# anchor.net
KiCad netlist of a schematic drawn in EAGLE
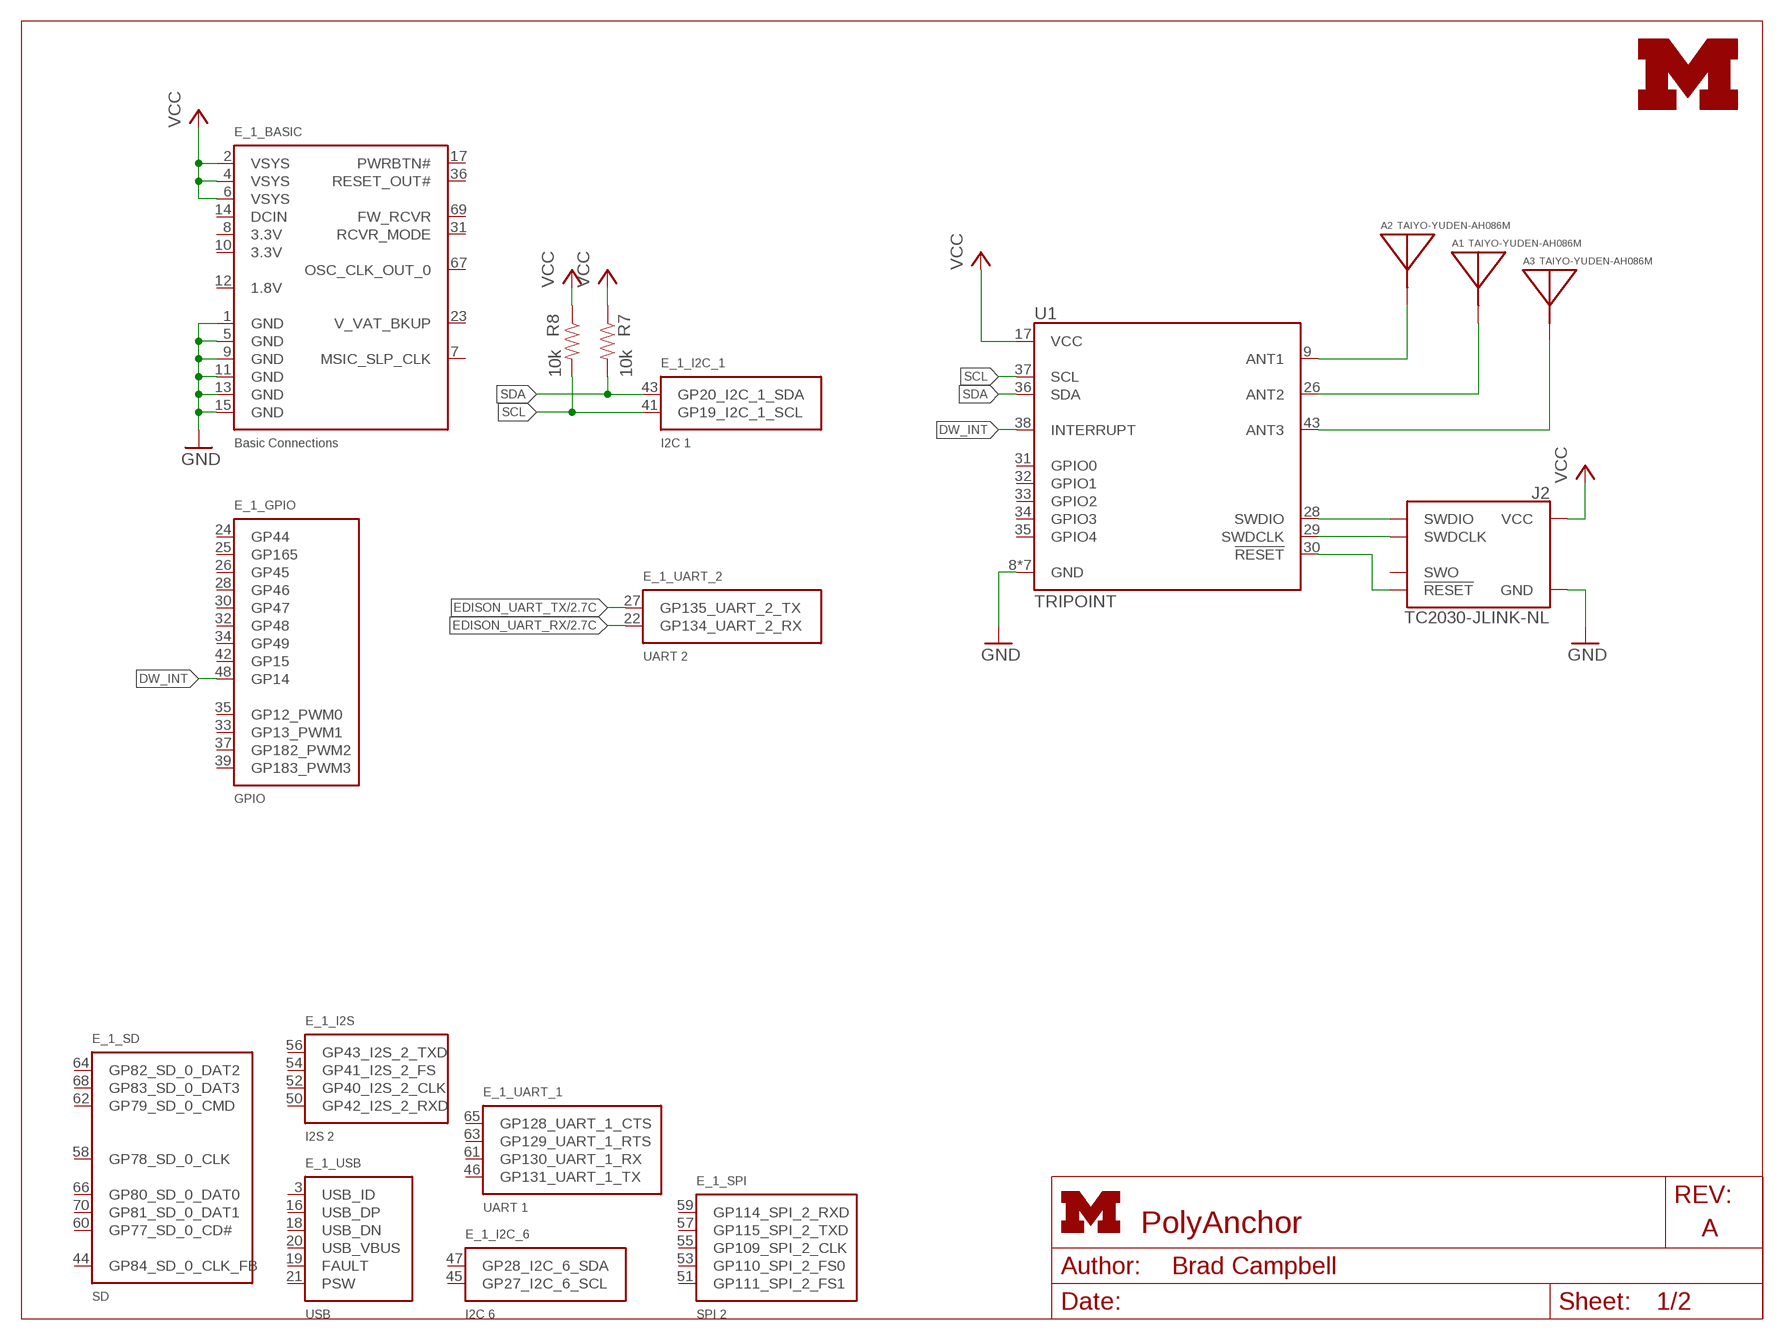
[diagram p0: schematic, sheet 1]
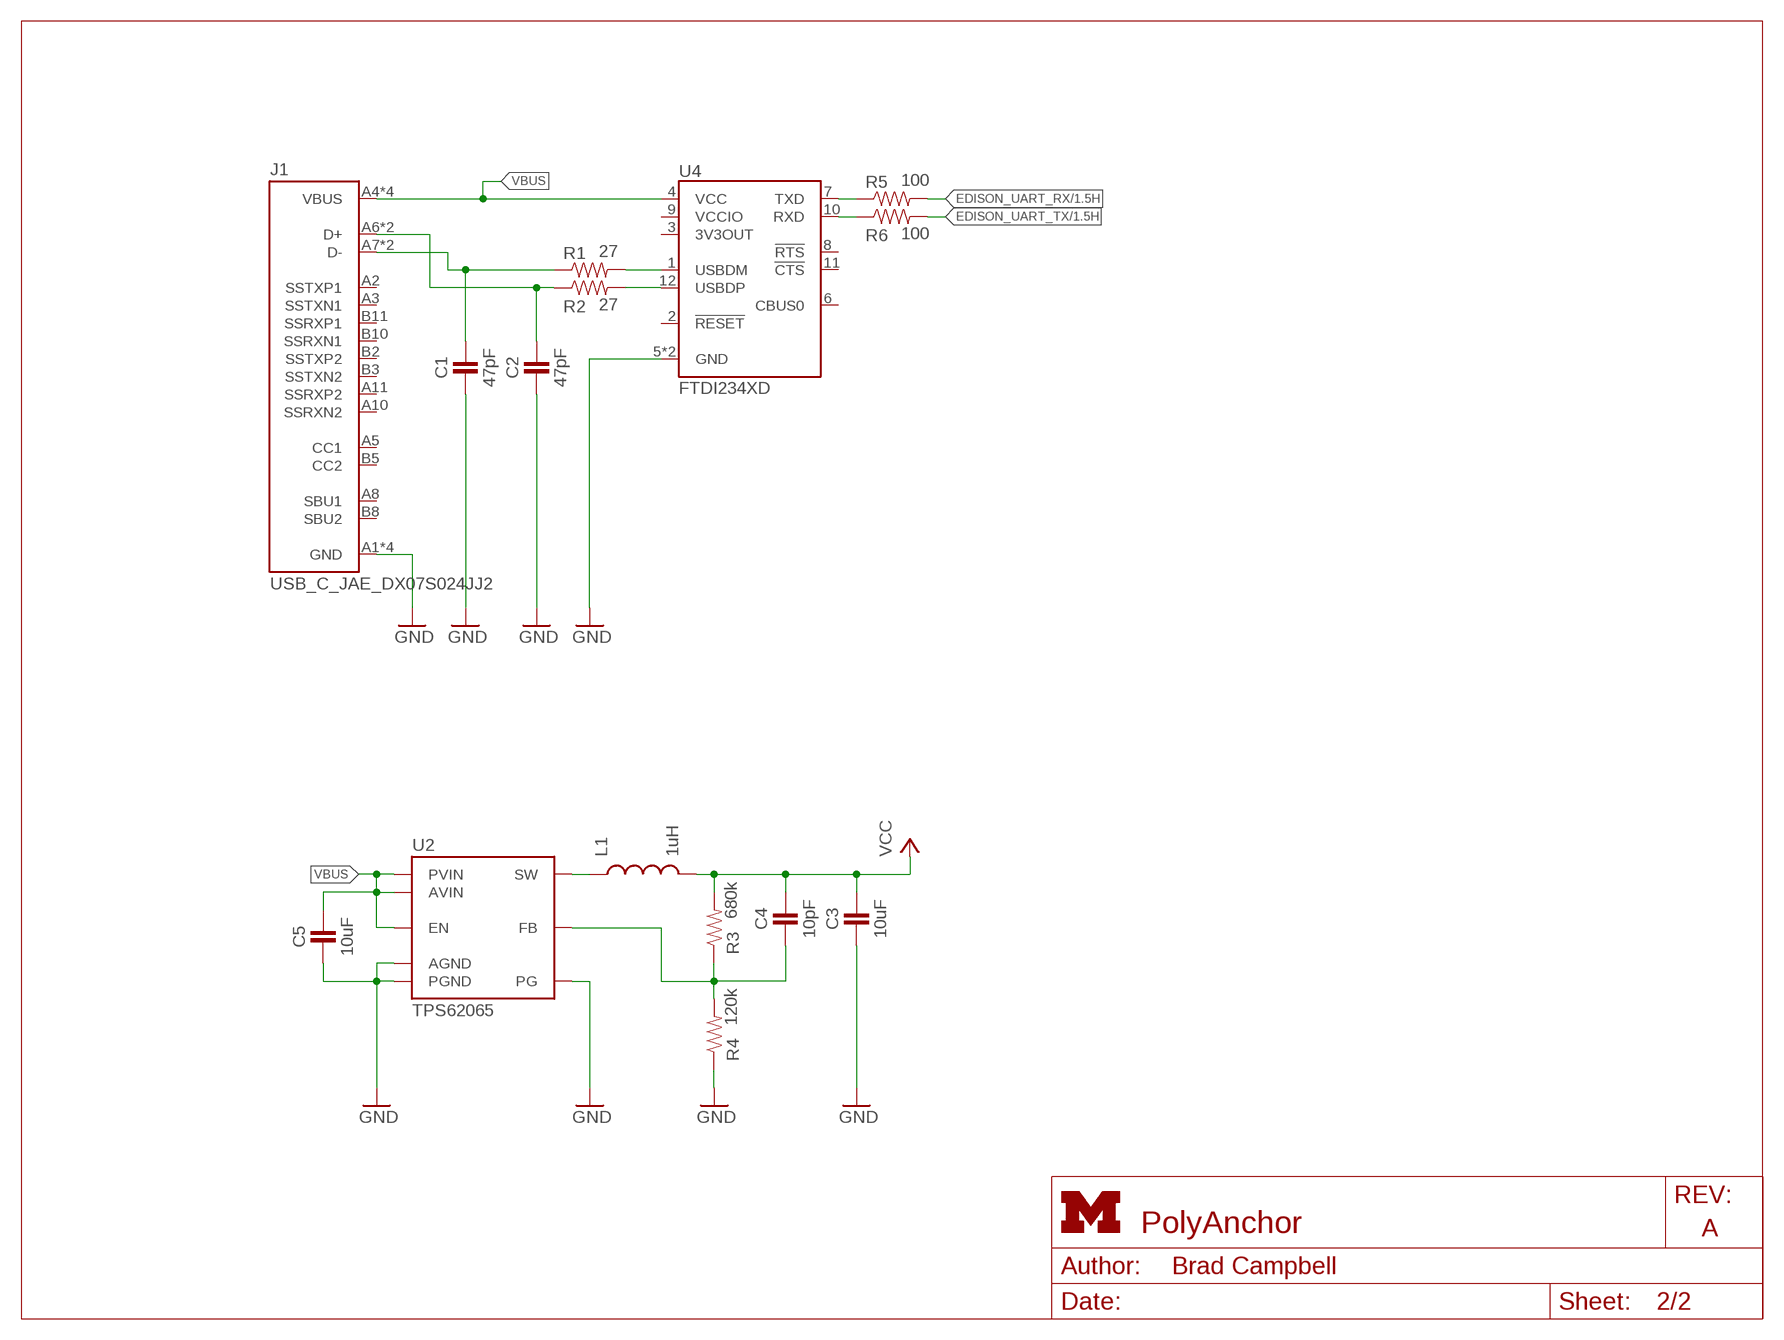
[diagram p1: schematic, sheet 2]

(export (version "E")
  (design (tool "Eeschema 10.0.6"))
  (components
    (comp (ref "C1")
      (value "47pF")
      (footprint "eagle-import:0402_CAP")
      (libsource (lib "eagle-import") (part "CAPACITOR"))
    )
    (comp (ref "C2")
      (value "47pF")
      (footprint "eagle-import:0402_CAP")
      (libsource (lib "eagle-import") (part "CAPACITOR"))
    )
    (comp (ref "C3")
      (value "10uF")
      (footprint "eagle-import:0603_CAP")
      (libsource (lib "eagle-import") (part "CAPACITOR0603_CAP"))
    )
    (comp (ref "C4")
      (value "10pF")
      (footprint "eagle-import:0402_CAP")
      (libsource (lib "eagle-import") (part "CAPACITOR"))
    )
    (comp (ref "C5")
      (value "10uF")
      (footprint "eagle-import:0603_CAP")
      (libsource (lib "eagle-import") (part "CAPACITOR0603_CAP"))
    )
    (comp (ref "J1")
      (value "USB_C_JAE_DX07S024JJ2")
      (footprint "eagle-import:DX07S024JJ2")
      (libsource (lib "eagle-import") (part "USB_C_JAE_DX07S024JJ2"))
    )
    (comp (ref "L1")
      (value "1uH")
      (footprint "eagle-import:1210")
      (libsource (lib "eagle-import") (part "INDUCTOR1210"))
    )
    (comp (ref "R1")
      (value "27")
      (footprint "eagle-import:0402_RES")
      (libsource (lib "eagle-import") (part "RESISTOR0402_RES"))
    )
    (comp (ref "R2")
      (value "27")
      (footprint "eagle-import:0402_RES")
      (libsource (lib "eagle-import") (part "RESISTOR0402_RES"))
    )
    (comp (ref "R3")
      (value "680k")
      (footprint "eagle-import:0402_RES")
      (libsource (lib "eagle-import") (part "RESISTOR0402_RES"))
    )
    (comp (ref "R4")
      (value "120k")
      (footprint "eagle-import:0402_RES")
      (libsource (lib "eagle-import") (part "RESISTOR0402_RES"))
    )
    (comp (ref "R5")
      (value "100")
      (footprint "eagle-import:0402_RES")
      (libsource (lib "eagle-import") (part "RESISTOR0402_RES"))
    )
    (comp (ref "R6")
      (value "100")
      (footprint "eagle-import:0402_RES")
      (libsource (lib "eagle-import") (part "RESISTOR0402_RES"))
    )
    (comp (ref "U2")
      (value "TPS62065")
      (footprint "eagle-import:S-PWSON-N8")
      (libsource (lib "eagle-import") (part "TPS62065"))
    )
    (comp (ref "U4")
      (value "FTDI234XD")
      (footprint "eagle-import:DFN-12_3MM")
      (libsource (lib "eagle-import") (part "FTDI234XD"))
    )
    (comp (ref "A1")
      (value "TAIYO-YUDEN-AH086M")
      (footprint "eagle-import:TAIYO-YUDEN-AH086M")
      (libsource (lib "eagle-import") (part "TAIYO-YUDEN-AH086M"))
    )
    (comp (ref "A2")
      (value "TAIYO-YUDEN-AH086M")
      (footprint "eagle-import:TAIYO-YUDEN-AH086M")
      (libsource (lib "eagle-import") (part "TAIYO-YUDEN-AH086M"))
    )
    (comp (ref "A3")
      (value "TAIYO-YUDEN-AH086M")
      (footprint "eagle-import:TAIYO-YUDEN-AH086M")
      (libsource (lib "eagle-import") (part "TAIYO-YUDEN-AH086M"))
    )
    (comp (ref "E_1")
      (value "EDISON_CONNECTOR_SEGMENTED")
      (footprint "eagle-import:EDISON_DAUGHTER")
      (libsource (lib "eagle-import") (part "EDISON_CONNECTOR_SEGMENTED"))
    )
    (comp (ref "J2")
      (value "TC2030-JLINK-NL")
      (footprint "eagle-import:TC2030-IDC-NL")
      (libsource (lib "eagle-import") (part "TC2030-JLINK-NL"))
    )
    (comp (ref "LOGO1")
      (value "UMICH_SOLID_MEDIUM")
      (footprint "eagle-import:UMICH_SOLID_200MIL")
      (libsource (lib "eagle-import") (part "UMICH_SOLID_MEDIUM"))
    )
    (comp (ref "R7")
      (value "10k")
      (footprint "eagle-import:0402_RES")
      (libsource (lib "eagle-import") (part "RESISTOR0402_RES"))
    )
    (comp (ref "R8")
      (value "10k")
      (footprint "eagle-import:0402_RES")
      (libsource (lib "eagle-import") (part "RESISTOR0402_RES"))
    )
    (comp (ref "U1")
      (value "TRIPOINT")
      (footprint "eagle-import:TRIPOINT")
      (libsource (lib "eagle-import") (part "TRIPOINT"))
    )
  )
  (nets
    (net (code "1") (name "DW_INT") (class "Default")
      (node (ref "E_1") (pin "48") (pinfunction "GP14_48") (pintype "bidirectional"))
      (node (ref "U1") (pin "38") (pinfunction "INTERRUPT_38") (pintype "bidirectional"))
    )
    (net (code "2") (name "EDISON_UART_RX") (class "Default")
      (node (ref "E_1") (pin "22") (pinfunction "GP134_UART_2_RX_22") (pintype "bidirectional"))
      (node (ref "R5") (pin "2") (pinfunction "2_2") (pintype "passive"))
    )
    (net (code "3") (name "EDISON_UART_TX") (class "Default")
      (node (ref "E_1") (pin "27") (pinfunction "GP135_UART_2_TX_27") (pintype "bidirectional"))
      (node (ref "R6") (pin "2") (pinfunction "2_2") (pintype "passive"))
    )
    (net (code "4") (name "GND") (class "Default")
      (node (ref "C1") (pin "2") (pinfunction "2_2") (pintype "bidirectional"))
      (node (ref "C2") (pin "2") (pinfunction "2_2") (pintype "bidirectional"))
      (node (ref "C3") (pin "2") (pinfunction "2_2") (pintype "bidirectional"))
      (node (ref "C5") (pin "2") (pinfunction "2_2") (pintype "bidirectional"))
      (node (ref "E_1") (pin "1") (pinfunction "GND_1") (pintype "bidirectional"))
      (node (ref "E_1") (pin "11") (pinfunction "GND_11") (pintype "bidirectional"))
      (node (ref "E_1") (pin "13") (pinfunction "GND_13") (pintype "bidirectional"))
      (node (ref "E_1") (pin "15") (pinfunction "GND_15") (pintype "bidirectional"))
      (node (ref "E_1") (pin "5") (pinfunction "GND_5") (pintype "bidirectional"))
      (node (ref "E_1") (pin "9") (pinfunction "GND_9") (pintype "bidirectional"))
      (node (ref "J1") (pin "A1") (pinfunction "GND_A1") (pintype "bidirectional"))
      (node (ref "J1") (pin "A12") (pinfunction "GND_A12") (pintype "bidirectional"))
      (node (ref "J1") (pin "B1") (pinfunction "GND_B1") (pintype "bidirectional"))
      (node (ref "J1") (pin "B12") (pinfunction "GND_B12") (pintype "bidirectional"))
      (node (ref "J2") (pin "5") (pinfunction "GND_5") (pintype "bidirectional"))
      (node (ref "R4") (pin "1") (pinfunction "1_1") (pintype "passive"))
      (node (ref "U1") (pin "10") (pinfunction "GND_10") (pintype "bidirectional"))
      (node (ref "U1") (pin "18") (pinfunction "GND_18") (pintype "bidirectional"))
      (node (ref "U1") (pin "25") (pinfunction "GND_25") (pintype "bidirectional"))
      (node (ref "U1") (pin "27") (pinfunction "GND_27") (pintype "bidirectional"))
      (node (ref "U1") (pin "42") (pinfunction "GND_42") (pintype "bidirectional"))
      (node (ref "U1") (pin "44") (pinfunction "GND_44") (pintype "bidirectional"))
      (node (ref "U1") (pin "8") (pinfunction "GND_8") (pintype "bidirectional"))
      (node (ref "U2") (pin "1") (pinfunction "PGND_1") (pintype "bidirectional"))
      (node (ref "U2") (pin "3") (pinfunction "AGND_3") (pintype "bidirectional"))
      (node (ref "U2") (pin "6") (pinfunction "PG_6") (pintype "bidirectional"))
      (node (ref "U2") (pin "P$1") (pinfunction "PGND_P$1") (pintype "bidirectional"))
      (node (ref "U4") (pin "13") (pinfunction "GND_13") (pintype "bidirectional"))
      (node (ref "U4") (pin "5") (pinfunction "GND_5") (pintype "bidirectional"))
    )
    (net (code "5") (name "Net-(A1-ANTENNA)") (class "Default")
      (node (ref "A1") (pin "A") (pinfunction "ANTENNA_A") (pintype "bidirectional"))
      (node (ref "U1") (pin "26") (pinfunction "ANT2_26") (pintype "bidirectional"))
    )
    (net (code "6") (name "Net-(A2-ANTENNA)") (class "Default")
      (node (ref "A2") (pin "A") (pinfunction "ANTENNA_A") (pintype "bidirectional"))
      (node (ref "U1") (pin "9") (pinfunction "ANT1_9") (pintype "bidirectional"))
    )
    (net (code "7") (name "Net-(A3-ANTENNA)") (class "Default")
      (node (ref "A3") (pin "A") (pinfunction "ANTENNA_A") (pintype "bidirectional"))
      (node (ref "U1") (pin "43") (pinfunction "ANT3_43") (pintype "bidirectional"))
    )
    (net (code "8") (name "Net-(C1-Pad1)") (class "Default")
      (node (ref "C1") (pin "1") (pinfunction "1_1") (pintype "bidirectional"))
      (node (ref "J1") (pin "A7") (pinfunction "D-_A7") (pintype "bidirectional"))
      (node (ref "J1") (pin "B7") (pinfunction "D-_B7") (pintype "bidirectional"))
      (node (ref "R1") (pin "1") (pinfunction "1_1") (pintype "passive"))
    )
    (net (code "9") (name "Net-(C2-Pad1)") (class "Default")
      (node (ref "C2") (pin "1") (pinfunction "1_1") (pintype "bidirectional"))
      (node (ref "J1") (pin "A6") (pinfunction "D+_A6") (pintype "bidirectional"))
      (node (ref "J1") (pin "B6") (pinfunction "D+_B6") (pintype "bidirectional"))
      (node (ref "R2") (pin "1") (pinfunction "1_1") (pintype "passive"))
    )
    (net (code "10") (name "Net-(J2-SWDCLK)") (class "Default")
      (node (ref "J2") (pin "4") (pinfunction "SWDCLK_4") (pintype "bidirectional"))
      (node (ref "U1") (pin "29") (pinfunction "SWDCLK_29") (pintype "bidirectional"))
    )
    (net (code "11") (name "Net-(J2-SWDIO)") (class "Default")
      (node (ref "J2") (pin "2") (pinfunction "SWDIO_2") (pintype "bidirectional"))
      (node (ref "U1") (pin "28") (pinfunction "SWDIO_28") (pintype "bidirectional"))
    )
    (net (code "12") (name "Net-(J2-~{RESET})") (class "Default")
      (node (ref "J2") (pin "3") (pinfunction "~{RESET}_3") (pintype "bidirectional"))
      (node (ref "U1") (pin "30") (pinfunction "~{RESET}_30") (pintype "bidirectional"))
    )
    (net (code "13") (name "Net-(U2-FB)") (class "Default")
      (node (ref "C4") (pin "2") (pinfunction "2_2") (pintype "bidirectional"))
      (node (ref "R3") (pin "1") (pinfunction "1_1") (pintype "passive"))
      (node (ref "R4") (pin "2") (pinfunction "2_2") (pintype "passive"))
      (node (ref "U2") (pin "4") (pinfunction "FB_4") (pintype "bidirectional"))
    )
    (net (code "14") (name "Net-(U2-SW)") (class "Default")
      (node (ref "L1") (pin "1") (pinfunction "1_1") (pintype "passive"))
      (node (ref "U2") (pin "2") (pinfunction "SW_2") (pintype "bidirectional"))
    )
    (net (code "15") (name "Net-(U4-RXD)") (class "Default")
      (node (ref "R6") (pin "1") (pinfunction "1_1") (pintype "passive"))
      (node (ref "U4") (pin "10") (pinfunction "RXD_10") (pintype "bidirectional"))
    )
    (net (code "16") (name "Net-(U4-TXD)") (class "Default")
      (node (ref "R5") (pin "1") (pinfunction "1_1") (pintype "passive"))
      (node (ref "U4") (pin "7") (pinfunction "TXD_7") (pintype "bidirectional"))
    )
    (net (code "17") (name "Net-(U4-USBDM)") (class "Default")
      (node (ref "R1") (pin "2") (pinfunction "2_2") (pintype "passive"))
      (node (ref "U4") (pin "1") (pinfunction "USBDM_1") (pintype "bidirectional"))
    )
    (net (code "18") (name "Net-(U4-USBDP)") (class "Default")
      (node (ref "R2") (pin "2") (pinfunction "2_2") (pintype "passive"))
      (node (ref "U4") (pin "12") (pinfunction "USBDP_12") (pintype "bidirectional"))
    )
    (net (code "19") (name "SCL") (class "Default")
      (node (ref "E_1") (pin "41") (pinfunction "GP19_I2C_1_SCL_41") (pintype "bidirectional"))
      (node (ref "R8") (pin "2") (pinfunction "2_2") (pintype "passive"))
      (node (ref "U1") (pin "37") (pinfunction "SCL_37") (pintype "bidirectional"))
    )
    (net (code "20") (name "SDA") (class "Default")
      (node (ref "E_1") (pin "43") (pinfunction "GP20_I2C_1_SDA_43") (pintype "bidirectional"))
      (node (ref "R7") (pin "2") (pinfunction "2_2") (pintype "passive"))
      (node (ref "U1") (pin "36") (pinfunction "SDA_36") (pintype "bidirectional"))
    )
    (net (code "21") (name "VBUS") (class "Default")
      (node (ref "C5") (pin "1") (pinfunction "1_1") (pintype "bidirectional"))
      (node (ref "J1") (pin "A4") (pinfunction "VBUS_A4") (pintype "bidirectional"))
      (node (ref "J1") (pin "A9") (pinfunction "VBUS_A9") (pintype "bidirectional"))
      (node (ref "J1") (pin "B4") (pinfunction "VBUS_B4") (pintype "bidirectional"))
      (node (ref "J1") (pin "B9") (pinfunction "VBUS_B9") (pintype "bidirectional"))
      (node (ref "U2") (pin "5") (pinfunction "EN_5") (pintype "bidirectional"))
      (node (ref "U2") (pin "7") (pinfunction "AVIN_7") (pintype "bidirectional"))
      (node (ref "U2") (pin "8") (pinfunction "PVIN_8") (pintype "bidirectional"))
      (node (ref "U4") (pin "4") (pinfunction "VCC_4") (pintype "bidirectional"))
    )
    (net (code "22") (name "VCC") (class "Default")
      (node (ref "C3") (pin "1") (pinfunction "1_1") (pintype "bidirectional"))
      (node (ref "C4") (pin "1") (pinfunction "1_1") (pintype "bidirectional"))
      (node (ref "E_1") (pin "2") (pinfunction "VSYS_2") (pintype "bidirectional"))
      (node (ref "E_1") (pin "4") (pinfunction "VSYS_4") (pintype "bidirectional"))
      (node (ref "E_1") (pin "6") (pinfunction "VSYS_6") (pintype "bidirectional"))
      (node (ref "J2") (pin "1") (pinfunction "VCC_1") (pintype "bidirectional"))
      (node (ref "L1") (pin "2") (pinfunction "2_2") (pintype "passive"))
      (node (ref "R3") (pin "2") (pinfunction "2_2") (pintype "passive"))
      (node (ref "R7") (pin "1") (pinfunction "1_1") (pintype "passive"))
      (node (ref "R8") (pin "1") (pinfunction "1_1") (pintype "passive"))
      (node (ref "U1") (pin "17") (pinfunction "VCC_17") (pintype "bidirectional"))
    )
    (net (code "23") (name "unconnected-(E_1A-1.8V-Pad12)") (class "Default")
      (node (ref "E_1") (pin "12") (pinfunction "1.8V_12") (pintype "bidirectional"))
    )
    (net (code "24") (name "unconnected-(E_1A-3.3V-Pad8)") (class "Default")
      (node (ref "E_1") (pin "8") (pinfunction "3.3V_8") (pintype "bidirectional"))
    )
    (net (code "25") (name "unconnected-(E_1A-3.3V-Pad10)") (class "Default")
      (node (ref "E_1") (pin "10") (pinfunction "3.3V_10") (pintype "bidirectional"))
    )
    (net (code "26") (name "unconnected-(E_1A-DCIN-Pad14)") (class "Default")
      (node (ref "E_1") (pin "14") (pinfunction "DCIN_14") (pintype "bidirectional"))
    )
    (net (code "27") (name "unconnected-(E_1A-FW_RCVR-Pad69)") (class "Default")
      (node (ref "E_1") (pin "69") (pinfunction "FW_RCVR_69") (pintype "bidirectional"))
    )
    (net (code "28") (name "unconnected-(E_1A-MSIC_SLP_CLK-Pad7)") (class "Default")
      (node (ref "E_1") (pin "7") (pinfunction "MSIC_SLP_CLK_7") (pintype "bidirectional"))
    )
    (net (code "29") (name "unconnected-(E_1A-OSC_CLK_OUT_0-Pad67)") (class "Default")
      (node (ref "E_1") (pin "67") (pinfunction "OSC_CLK_OUT_0_67") (pintype "bidirectional"))
    )
    (net (code "30") (name "unconnected-(E_1A-PWRBTN#-Pad17)") (class "Default")
      (node (ref "E_1") (pin "17") (pinfunction "PWRBTN#_17") (pintype "bidirectional"))
    )
    (net (code "31") (name "unconnected-(E_1A-RCVR_MODE-Pad31)") (class "Default")
      (node (ref "E_1") (pin "31") (pinfunction "RCVR_MODE_31") (pintype "bidirectional"))
    )
    (net (code "32") (name "unconnected-(E_1A-RESET_OUT#-Pad36)") (class "Default")
      (node (ref "E_1") (pin "36") (pinfunction "RESET_OUT#_36") (pintype "bidirectional"))
    )
    (net (code "33") (name "unconnected-(E_1A-V_VAT_BKUP-Pad23)") (class "Default")
      (node (ref "E_1") (pin "23") (pinfunction "V_VAT_BKUP_23") (pintype "bidirectional"))
    )
    (net (code "34") (name "unconnected-(E_1B-GP12_PWM0-Pad35)") (class "Default")
      (node (ref "E_1") (pin "35") (pinfunction "GP12_PWM0_35") (pintype "bidirectional"))
    )
    (net (code "35") (name "unconnected-(E_1B-GP13_PWM1-Pad33)") (class "Default")
      (node (ref "E_1") (pin "33") (pinfunction "GP13_PWM1_33") (pintype "bidirectional"))
    )
    (net (code "36") (name "unconnected-(E_1B-GP15-Pad42)") (class "Default")
      (node (ref "E_1") (pin "42") (pinfunction "GP15_42") (pintype "bidirectional"))
    )
    (net (code "37") (name "unconnected-(E_1B-GP44-Pad24)") (class "Default")
      (node (ref "E_1") (pin "24") (pinfunction "GP44_24") (pintype "bidirectional"))
    )
    (net (code "38") (name "unconnected-(E_1B-GP45-Pad26)") (class "Default")
      (node (ref "E_1") (pin "26") (pinfunction "GP45_26") (pintype "bidirectional"))
    )
    (net (code "39") (name "unconnected-(E_1B-GP46-Pad28)") (class "Default")
      (node (ref "E_1") (pin "28") (pinfunction "GP46_28") (pintype "bidirectional"))
    )
    (net (code "40") (name "unconnected-(E_1B-GP47-Pad30)") (class "Default")
      (node (ref "E_1") (pin "30") (pinfunction "GP47_30") (pintype "bidirectional"))
    )
    (net (code "41") (name "unconnected-(E_1B-GP48-Pad32)") (class "Default")
      (node (ref "E_1") (pin "32") (pinfunction "GP48_32") (pintype "bidirectional"))
    )
    (net (code "42") (name "unconnected-(E_1B-GP49-Pad34)") (class "Default")
      (node (ref "E_1") (pin "34") (pinfunction "GP49_34") (pintype "bidirectional"))
    )
    (net (code "43") (name "unconnected-(E_1B-GP165-Pad25)") (class "Default")
      (node (ref "E_1") (pin "25") (pinfunction "GP165_25") (pintype "bidirectional"))
    )
    (net (code "44") (name "unconnected-(E_1B-GP182_PWM2-Pad37)") (class "Default")
      (node (ref "E_1") (pin "37") (pinfunction "GP182_PWM2_37") (pintype "bidirectional"))
    )
    (net (code "45") (name "unconnected-(E_1B-GP183_PWM3-Pad39)") (class "Default")
      (node (ref "E_1") (pin "39") (pinfunction "GP183_PWM3_39") (pintype "bidirectional"))
    )
    (net (code "46") (name "unconnected-(E_1D-GP27_I2C_6_SCL-Pad45)") (class "Default")
      (node (ref "E_1") (pin "45") (pinfunction "GP27_I2C_6_SCL_45") (pintype "bidirectional"))
    )
    (net (code "47") (name "unconnected-(E_1D-GP28_I2C_6_SDA-Pad47)") (class "Default")
      (node (ref "E_1") (pin "47") (pinfunction "GP28_I2C_6_SDA_47") (pintype "bidirectional"))
    )
    (net (code "48") (name "unconnected-(E_1E-GP40_I2S_2_CLK-Pad52)") (class "Default")
      (node (ref "E_1") (pin "52") (pinfunction "GP40_I2S_2_CLK_52") (pintype "bidirectional"))
    )
    (net (code "49") (name "unconnected-(E_1E-GP41_I2S_2_FS-Pad54)") (class "Default")
      (node (ref "E_1") (pin "54") (pinfunction "GP41_I2S_2_FS_54") (pintype "bidirectional"))
    )
    (net (code "50") (name "unconnected-(E_1E-GP42_I2S_2_RXD-Pad50)") (class "Default")
      (node (ref "E_1") (pin "50") (pinfunction "GP42_I2S_2_RXD_50") (pintype "bidirectional"))
    )
    (net (code "51") (name "unconnected-(E_1E-GP43_I2S_2_TXD-Pad56)") (class "Default")
      (node (ref "E_1") (pin "56") (pinfunction "GP43_I2S_2_TXD_56") (pintype "bidirectional"))
    )
    (net (code "52") (name "unconnected-(E_1F-GP77_SD_0_CD#-Pad60)") (class "Default")
      (node (ref "E_1") (pin "60") (pinfunction "GP77_SD_0_CD#_60") (pintype "bidirectional"))
    )
    (net (code "53") (name "unconnected-(E_1F-GP78_SD_0_CLK-Pad58)") (class "Default")
      (node (ref "E_1") (pin "58") (pinfunction "GP78_SD_0_CLK_58") (pintype "bidirectional"))
    )
    (net (code "54") (name "unconnected-(E_1F-GP79_SD_0_CMD-Pad62)") (class "Default")
      (node (ref "E_1") (pin "62") (pinfunction "GP79_SD_0_CMD_62") (pintype "bidirectional"))
    )
    (net (code "55") (name "unconnected-(E_1F-GP80_SD_0_DAT0-Pad66)") (class "Default")
      (node (ref "E_1") (pin "66") (pinfunction "GP80_SD_0_DAT0_66") (pintype "bidirectional"))
    )
    (net (code "56") (name "unconnected-(E_1F-GP81_SD_0_DAT1-Pad70)") (class "Default")
      (node (ref "E_1") (pin "70") (pinfunction "GP81_SD_0_DAT1_70") (pintype "bidirectional"))
    )
    (net (code "57") (name "unconnected-(E_1F-GP82_SD_0_DAT2-Pad64)") (class "Default")
      (node (ref "E_1") (pin "64") (pinfunction "GP82_SD_0_DAT2_64") (pintype "bidirectional"))
    )
    (net (code "58") (name "unconnected-(E_1F-GP83_SD_0_DAT3-Pad68)") (class "Default")
      (node (ref "E_1") (pin "68") (pinfunction "GP83_SD_0_DAT3_68") (pintype "bidirectional"))
    )
    (net (code "59") (name "unconnected-(E_1F-GP84_SD_0_CLK_FB-Pad44)") (class "Default")
      (node (ref "E_1") (pin "44") (pinfunction "GP84_SD_0_CLK_FB_44") (pintype "bidirectional"))
    )
    (net (code "60") (name "unconnected-(E_1G-GP109_SPI_2_CLK-Pad55)") (class "Default")
      (node (ref "E_1") (pin "55") (pinfunction "GP109_SPI_2_CLK_55") (pintype "bidirectional"))
    )
    (net (code "61") (name "unconnected-(E_1G-GP110_SPI_2_FS0-Pad53)") (class "Default")
      (node (ref "E_1") (pin "53") (pinfunction "GP110_SPI_2_FS0_53") (pintype "bidirectional"))
    )
    (net (code "62") (name "unconnected-(E_1G-GP111_SPI_2_FS1-Pad51)") (class "Default")
      (node (ref "E_1") (pin "51") (pinfunction "GP111_SPI_2_FS1_51") (pintype "bidirectional"))
    )
    (net (code "63") (name "unconnected-(E_1G-GP114_SPI_2_RXD-Pad59)") (class "Default")
      (node (ref "E_1") (pin "59") (pinfunction "GP114_SPI_2_RXD_59") (pintype "bidirectional"))
    )
    (net (code "64") (name "unconnected-(E_1G-GP115_SPI_2_TXD-Pad57)") (class "Default")
      (node (ref "E_1") (pin "57") (pinfunction "GP115_SPI_2_TXD_57") (pintype "bidirectional"))
    )
    (net (code "65") (name "unconnected-(E_1H-GP128_UART_1_CTS-Pad65)") (class "Default")
      (node (ref "E_1") (pin "65") (pinfunction "GP128_UART_1_CTS_65") (pintype "bidirectional"))
    )
    (net (code "66") (name "unconnected-(E_1H-GP129_UART_1_RTS-Pad63)") (class "Default")
      (node (ref "E_1") (pin "63") (pinfunction "GP129_UART_1_RTS_63") (pintype "bidirectional"))
    )
    (net (code "67") (name "unconnected-(E_1H-GP130_UART_1_RX-Pad61)") (class "Default")
      (node (ref "E_1") (pin "61") (pinfunction "GP130_UART_1_RX_61") (pintype "bidirectional"))
    )
    (net (code "68") (name "unconnected-(E_1H-GP131_UART_1_TX-Pad46)") (class "Default")
      (node (ref "E_1") (pin "46") (pinfunction "GP131_UART_1_TX_46") (pintype "bidirectional"))
    )
    (net (code "69") (name "unconnected-(E_1J-FAULT-Pad19)") (class "Default")
      (node (ref "E_1") (pin "19") (pinfunction "FAULT_19") (pintype "bidirectional"))
    )
    (net (code "70") (name "unconnected-(E_1J-PSW-Pad21)") (class "Default")
      (node (ref "E_1") (pin "21") (pinfunction "PSW_21") (pintype "bidirectional"))
    )
    (net (code "71") (name "unconnected-(E_1J-USB_DN-Pad18)") (class "Default")
      (node (ref "E_1") (pin "18") (pinfunction "USB_DN_18") (pintype "bidirectional"))
    )
    (net (code "72") (name "unconnected-(E_1J-USB_DP-Pad16)") (class "Default")
      (node (ref "E_1") (pin "16") (pinfunction "USB_DP_16") (pintype "bidirectional"))
    )
    (net (code "73") (name "unconnected-(E_1J-USB_ID-Pad3)") (class "Default")
      (node (ref "E_1") (pin "3") (pinfunction "USB_ID_3") (pintype "bidirectional"))
    )
    (net (code "74") (name "unconnected-(E_1J-USB_VBUS-Pad20)") (class "Default")
      (node (ref "E_1") (pin "20") (pinfunction "USB_VBUS_20") (pintype "bidirectional"))
    )
    (net (code "75") (name "unconnected-(J1-CC1-PadA5)") (class "Default")
      (node (ref "J1") (pin "A5") (pinfunction "CC1_A5") (pintype "bidirectional"))
    )
    (net (code "76") (name "unconnected-(J1-CC2-PadB5)") (class "Default")
      (node (ref "J1") (pin "B5") (pinfunction "CC2_B5") (pintype "bidirectional"))
    )
    (net (code "77") (name "unconnected-(J1-SBU1-PadA8)") (class "Default")
      (node (ref "J1") (pin "A8") (pinfunction "SBU1_A8") (pintype "bidirectional"))
    )
    (net (code "78") (name "unconnected-(J1-SBU2-PadB8)") (class "Default")
      (node (ref "J1") (pin "B8") (pinfunction "SBU2_B8") (pintype "bidirectional"))
    )
    (net (code "79") (name "unconnected-(J1-SSRXN1-PadB10)") (class "Default")
      (node (ref "J1") (pin "B10") (pinfunction "SSRXN1_B10") (pintype "bidirectional"))
    )
    (net (code "80") (name "unconnected-(J1-SSRXN2-PadA10)") (class "Default")
      (node (ref "J1") (pin "A10") (pinfunction "SSRXN2_A10") (pintype "bidirectional"))
    )
    (net (code "81") (name "unconnected-(J1-SSRXP1-PadB11)") (class "Default")
      (node (ref "J1") (pin "B11") (pinfunction "SSRXP1_B11") (pintype "bidirectional"))
    )
    (net (code "82") (name "unconnected-(J1-SSRXP2-PadA11)") (class "Default")
      (node (ref "J1") (pin "A11") (pinfunction "SSRXP2_A11") (pintype "bidirectional"))
    )
    (net (code "83") (name "unconnected-(J1-SSTXN1-PadA3)") (class "Default")
      (node (ref "J1") (pin "A3") (pinfunction "SSTXN1_A3") (pintype "bidirectional"))
    )
    (net (code "84") (name "unconnected-(J1-SSTXN2-PadB3)") (class "Default")
      (node (ref "J1") (pin "B3") (pinfunction "SSTXN2_B3") (pintype "bidirectional"))
    )
    (net (code "85") (name "unconnected-(J1-SSTXP1-PadA2)") (class "Default")
      (node (ref "J1") (pin "A2") (pinfunction "SSTXP1_A2") (pintype "bidirectional"))
    )
    (net (code "86") (name "unconnected-(J1-SSTXP2-PadB2)") (class "Default")
      (node (ref "J1") (pin "B2") (pinfunction "SSTXP2_B2") (pintype "bidirectional"))
    )
    (net (code "87") (name "unconnected-(J2-SWO-Pad6)") (class "Default")
      (node (ref "J2") (pin "6") (pinfunction "SWO_6") (pintype "bidirectional"))
    )
    (net (code "88") (name "unconnected-(U1-GPIO0-Pad31)") (class "Default")
      (node (ref "U1") (pin "31") (pinfunction "GPIO0_31") (pintype "bidirectional"))
    )
    (net (code "89") (name "unconnected-(U1-GPIO1-Pad32)") (class "Default")
      (node (ref "U1") (pin "32") (pinfunction "GPIO1_32") (pintype "bidirectional"))
    )
    (net (code "90") (name "unconnected-(U1-GPIO2-Pad33)") (class "Default")
      (node (ref "U1") (pin "33") (pinfunction "GPIO2_33") (pintype "bidirectional"))
    )
    (net (code "91") (name "unconnected-(U1-GPIO3-Pad34)") (class "Default")
      (node (ref "U1") (pin "34") (pinfunction "GPIO3_34") (pintype "bidirectional"))
    )
    (net (code "92") (name "unconnected-(U1-GPIO4-Pad35)") (class "Default")
      (node (ref "U1") (pin "35") (pinfunction "GPIO4_35") (pintype "bidirectional"))
    )
    (net (code "93") (name "unconnected-(U4-3V3OUT-Pad3)") (class "Default")
      (node (ref "U4") (pin "3") (pinfunction "3V3OUT_3") (pintype "bidirectional"))
    )
    (net (code "94") (name "unconnected-(U4-CBUS0-Pad6)") (class "Default")
      (node (ref "U4") (pin "6") (pinfunction "CBUS0_6") (pintype "bidirectional"))
    )
    (net (code "95") (name "unconnected-(U4-VCCIO-Pad9)") (class "Default")
      (node (ref "U4") (pin "9") (pinfunction "VCCIO_9") (pintype "bidirectional"))
    )
    (net (code "96") (name "unconnected-(U4-~{CTS}-Pad11)") (class "Default")
      (node (ref "U4") (pin "11") (pinfunction "~{CTS}_11") (pintype "bidirectional"))
    )
    (net (code "97") (name "unconnected-(U4-~{RESET}-Pad2)") (class "Default")
      (node (ref "U4") (pin "2") (pinfunction "~{RESET}_2") (pintype "bidirectional"))
    )
    (net (code "98") (name "unconnected-(U4-~{RTS}-Pad8)") (class "Default")
      (node (ref "U4") (pin "8") (pinfunction "~{RTS}_8") (pintype "bidirectional"))
    )
  )
)
